# ES8388.net
KiCad netlist of a schematic drawn in Altium Designer
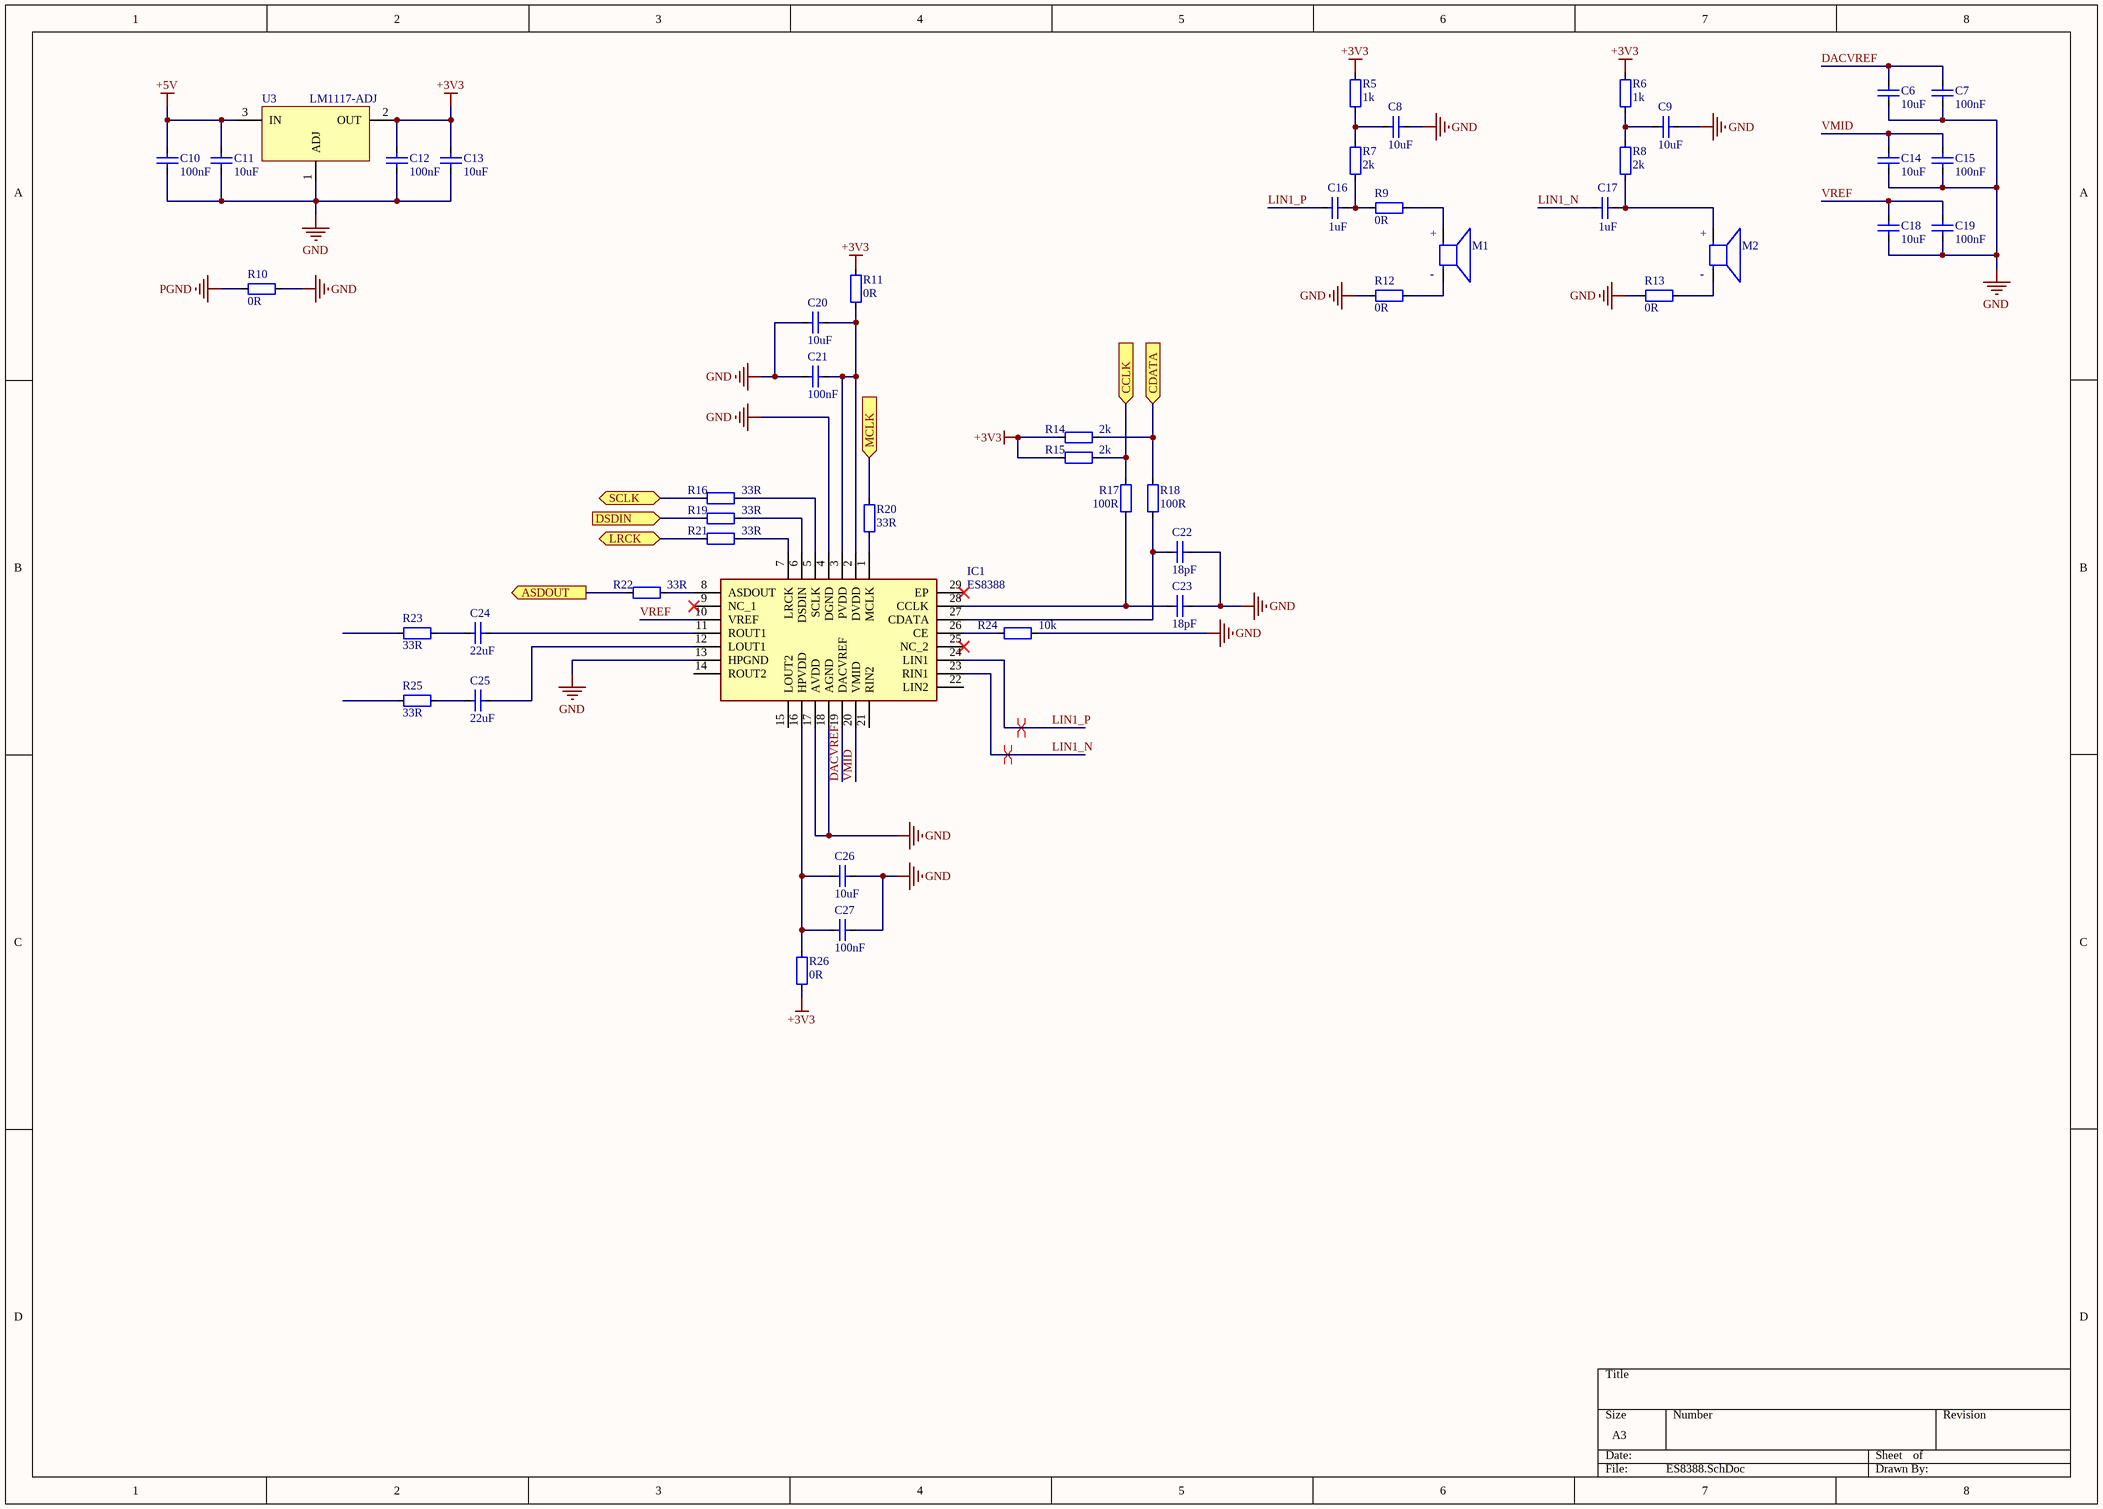
[diagram p0: ES8388.SchDoc]

(export (version "E")
  (design (tool "Eeschema 10.0.6"))
  (components
    (comp (ref "C6")
      (value "10uF")
      (footprint "CAP_0603")
      (description "Capacitor")
      (fields (field (name "PUBLISHER") "Altium Limited"))
      (libsource (lib "My Library") (part "CapSMD"))
    )
    (comp (ref "C7")
      (value "100nF")
      (footprint "CAP_0603")
      (description "Capacitor")
      (fields (field (name "PUBLISHER") "Altium Limited"))
      (libsource (lib "My Library") (part "CapSMD"))
    )
    (comp (ref "C8")
      (value "10uF")
      (footprint "CAP_0603")
      (description "Capacitor")
      (fields (field (name "PUBLISHER") "Altium Limited"))
      (libsource (lib "My Library") (part "CapSMD"))
    )
    (comp (ref "C9")
      (value "10uF")
      (footprint "CAP_0603")
      (description "Capacitor")
      (fields (field (name "PUBLISHER") "Altium Limited"))
      (libsource (lib "My Library") (part "CapSMD"))
    )
    (comp (ref "C10")
      (value "100nF")
      (footprint "CAP_0805")
      (description "Capacitor")
      (fields (field (name "PUBLISHER") "Altium Limited"))
      (libsource (lib "My Library") (part "CapSMD"))
    )
    (comp (ref "C11")
      (value "10uF")
      (footprint "CAP_0805")
      (description "Capacitor")
      (fields (field (name "PUBLISHER") "Altium Limited"))
      (libsource (lib "My Library") (part "CapSMD"))
    )
    (comp (ref "C12")
      (value "100nF")
      (footprint "CAP_0805")
      (description "Capacitor")
      (fields (field (name "PUBLISHER") "Altium Limited"))
      (libsource (lib "My Library") (part "CapSMD"))
    )
    (comp (ref "C13")
      (value "10uF")
      (footprint "CAP_0805")
      (description "Capacitor")
      (fields (field (name "PUBLISHER") "Altium Limited"))
      (libsource (lib "My Library") (part "CapSMD"))
    )
    (comp (ref "C14")
      (value "10uF")
      (footprint "CAP_0603")
      (description "Capacitor")
      (fields (field (name "PUBLISHER") "Altium Limited"))
      (libsource (lib "My Library") (part "CapSMD"))
    )
    (comp (ref "C15")
      (value "100nF")
      (footprint "CAP_0603")
      (description "Capacitor")
      (fields (field (name "PUBLISHER") "Altium Limited"))
      (libsource (lib "My Library") (part "CapSMD"))
    )
    (comp (ref "C16")
      (value "1uF")
      (footprint "CAP_0603")
      (description "Capacitor")
      (fields (field (name "PUBLISHER") "Altium Limited"))
      (libsource (lib "My Library") (part "CapSMD"))
    )
    (comp (ref "C17")
      (value "1uF")
      (footprint "CAP_0603")
      (description "Capacitor")
      (fields (field (name "PUBLISHER") "Altium Limited"))
      (libsource (lib "My Library") (part "CapSMD"))
    )
    (comp (ref "C18")
      (value "10uF")
      (footprint "CAP_0603")
      (description "Capacitor")
      (fields (field (name "PUBLISHER") "Altium Limited"))
      (libsource (lib "My Library") (part "CapSMD"))
    )
    (comp (ref "C19")
      (value "100nF")
      (footprint "CAP_0603")
      (description "Capacitor")
      (fields (field (name "PUBLISHER") "Altium Limited"))
      (libsource (lib "My Library") (part "CapSMD"))
    )
    (comp (ref "C20")
      (value "10uF")
      (footprint "CAP_0603")
      (description "Capacitor")
      (fields (field (name "PUBLISHER") "Altium Limited"))
      (libsource (lib "My Library") (part "CapSMD"))
    )
    (comp (ref "C21")
      (value "100nF")
      (footprint "CAP_0603")
      (description "Capacitor")
      (fields (field (name "PUBLISHER") "Altium Limited"))
      (libsource (lib "My Library") (part "CapSMD"))
    )
    (comp (ref "C22")
      (value "18pF")
      (footprint "CAP_0603")
      (description "Capacitor")
      (fields (field (name "PUBLISHER") "Altium Limited"))
      (libsource (lib "My Library") (part "CapSMD"))
    )
    (comp (ref "C23")
      (value "18pF")
      (footprint "CAP_0603")
      (description "Capacitor")
      (fields (field (name "PUBLISHER") "Altium Limited"))
      (libsource (lib "My Library") (part "CapSMD"))
    )
    (comp (ref "C24")
      (value "22uF")
      (footprint "CAP_0805")
      (description "Capacitor")
      (fields (field (name "PUBLISHER") "Altium Limited"))
      (libsource (lib "My Library") (part "CapSMD"))
    )
    (comp (ref "C25")
      (value "22uF")
      (footprint "CAP_0805")
      (description "Capacitor")
      (fields (field (name "PUBLISHER") "Altium Limited"))
      (libsource (lib "My Library") (part "CapSMD"))
    )
    (comp (ref "C26")
      (value "10uF")
      (footprint "CAP_0603")
      (description "Capacitor")
      (fields (field (name "PUBLISHER") "Altium Limited"))
      (libsource (lib "My Library") (part "CapSMD"))
    )
    (comp (ref "C27")
      (value "100nF")
      (footprint "CAP_0603")
      (description "Capacitor")
      (fields (field (name "PUBLISHER") "Altium Limited"))
      (libsource (lib "My Library") (part "CapSMD"))
    )
    (comp (ref "IC1") (value "ES8388") (footprint "ES8388") (libsource (lib "My Library") (part "ES8388")))
    (comp (ref "M1")
      (value "Microphone")
      (footprint "Microphone")
      (libsource (lib "My Library") (part "Microphone"))
    )
    (comp (ref "M2")
      (value "Microphone")
      (footprint "Microphone")
      (libsource (lib "My Library") (part "Microphone"))
    )
    (comp (ref "R5")
      (value "1k")
      (footprint "RES-SMD-0603")
      (description "Resistor")
      (fields
        (field (name "MANUFACTURER") "Generic Components")
        (field (name "PUBLISHER") "Altium Hobart Technology Centre")
      )
      (libsource (lib "My Library") (part "Resistor - SMD"))
    )
    (comp (ref "R6")
      (value "1k")
      (footprint "RES-SMD-0603")
      (description "Resistor")
      (fields
        (field (name "MANUFACTURER") "Generic Components")
        (field (name "PUBLISHER") "Altium Hobart Technology Centre")
      )
      (libsource (lib "My Library") (part "Resistor - SMD"))
    )
    (comp (ref "R7")
      (value "2k")
      (footprint "RES-SMD-0603")
      (description "Resistor")
      (fields
        (field (name "MANUFACTURER") "Generic Components")
        (field (name "PUBLISHER") "Altium Hobart Technology Centre")
      )
      (libsource (lib "My Library") (part "Resistor - SMD"))
    )
    (comp (ref "R8")
      (value "2k")
      (footprint "RES-SMD-0603")
      (description "Resistor")
      (fields
        (field (name "MANUFACTURER") "Generic Components")
        (field (name "PUBLISHER") "Altium Hobart Technology Centre")
      )
      (libsource (lib "My Library") (part "Resistor - SMD"))
    )
    (comp (ref "R9")
      (value "0R")
      (footprint "RES-SMD-0603")
      (description "Resistor")
      (fields
        (field (name "MANUFACTURER") "Generic Components")
        (field (name "PUBLISHER") "Altium Hobart Technology Centre")
      )
      (libsource (lib "My Library") (part "Resistor - SMD"))
    )
    (comp (ref "R10")
      (value "0R")
      (footprint "RES-SMD-0603")
      (description "Resistor")
      (fields
        (field (name "MANUFACTURER") "Generic Components")
        (field (name "PUBLISHER") "Altium Hobart Technology Centre")
      )
      (libsource (lib "My Library") (part "Resistor - SMD"))
    )
    (comp (ref "R11")
      (value "0R")
      (footprint "RES-SMD-0603")
      (description "Resistor")
      (fields
        (field (name "MANUFACTURER") "Generic Components")
        (field (name "PUBLISHER") "Altium Hobart Technology Centre")
      )
      (libsource (lib "My Library") (part "Resistor - SMD"))
    )
    (comp (ref "R12")
      (value "0R")
      (footprint "RES-SMD-0603")
      (description "Resistor")
      (fields
        (field (name "MANUFACTURER") "Generic Components")
        (field (name "PUBLISHER") "Altium Hobart Technology Centre")
      )
      (libsource (lib "My Library") (part "Resistor - SMD"))
    )
    (comp (ref "R13")
      (value "0R")
      (footprint "RES-SMD-0603")
      (description "Resistor")
      (fields
        (field (name "MANUFACTURER") "Generic Components")
        (field (name "PUBLISHER") "Altium Hobart Technology Centre")
      )
      (libsource (lib "My Library") (part "Resistor - SMD"))
    )
    (comp (ref "R14")
      (value "2k")
      (footprint "RES-SMD-0603")
      (description "Resistor")
      (fields
        (field (name "MANUFACTURER") "Generic Components")
        (field (name "PUBLISHER") "Altium Hobart Technology Centre")
      )
      (libsource (lib "My Library") (part "Resistor - SMD"))
    )
    (comp (ref "R15")
      (value "2k")
      (footprint "RES-SMD-0603")
      (description "Resistor")
      (fields
        (field (name "MANUFACTURER") "Generic Components")
        (field (name "PUBLISHER") "Altium Hobart Technology Centre")
      )
      (libsource (lib "My Library") (part "Resistor - SMD"))
    )
    (comp (ref "R16")
      (value "33R")
      (footprint "RES-SMD-0603")
      (description "Resistor")
      (fields
        (field (name "MANUFACTURER") "Generic Components")
        (field (name "PUBLISHER") "Altium Hobart Technology Centre")
      )
      (libsource (lib "My Library") (part "Resistor - SMD"))
    )
    (comp (ref "R17")
      (value "100R")
      (footprint "RES-SMD-0603")
      (description "Resistor")
      (fields
        (field (name "MANUFACTURER") "Generic Components")
        (field (name "PUBLISHER") "Altium Hobart Technology Centre")
      )
      (libsource (lib "My Library") (part "Resistor - SMD"))
    )
    (comp (ref "R18")
      (value "100R")
      (footprint "RES-SMD-0603")
      (description "Resistor")
      (fields
        (field (name "MANUFACTURER") "Generic Components")
        (field (name "PUBLISHER") "Altium Hobart Technology Centre")
      )
      (libsource (lib "My Library") (part "Resistor - SMD"))
    )
    (comp (ref "R19")
      (value "33R")
      (footprint "RES-SMD-0603")
      (description "Resistor")
      (fields
        (field (name "MANUFACTURER") "Generic Components")
        (field (name "PUBLISHER") "Altium Hobart Technology Centre")
      )
      (libsource (lib "My Library") (part "Resistor - SMD"))
    )
    (comp (ref "R20")
      (value "33R")
      (footprint "RES-SMD-0603")
      (description "Resistor")
      (fields
        (field (name "MANUFACTURER") "Generic Components")
        (field (name "PUBLISHER") "Altium Hobart Technology Centre")
      )
      (libsource (lib "My Library") (part "Resistor - SMD"))
    )
    (comp (ref "R21")
      (value "33R")
      (footprint "RES-SMD-0603")
      (description "Resistor")
      (fields
        (field (name "MANUFACTURER") "Generic Components")
        (field (name "PUBLISHER") "Altium Hobart Technology Centre")
      )
      (libsource (lib "My Library") (part "Resistor - SMD"))
    )
    (comp (ref "R22")
      (value "33R")
      (footprint "RES-SMD-0603")
      (description "Resistor")
      (fields
        (field (name "MANUFACTURER") "Generic Components")
        (field (name "PUBLISHER") "Altium Hobart Technology Centre")
      )
      (libsource (lib "My Library") (part "Resistor - SMD"))
    )
    (comp (ref "R23")
      (value "33R")
      (footprint "RES-SMD-0603")
      (description "Resistor")
      (fields
        (field (name "MANUFACTURER") "Generic Components")
        (field (name "PUBLISHER") "Altium Hobart Technology Centre")
      )
      (libsource (lib "My Library") (part "Resistor - SMD"))
    )
    (comp (ref "R24")
      (value "10k")
      (footprint "RES-SMD-0603")
      (description "Resistor")
      (fields
        (field (name "MANUFACTURER") "Generic Components")
        (field (name "PUBLISHER") "Altium Hobart Technology Centre")
      )
      (libsource (lib "My Library") (part "Resistor - SMD"))
    )
    (comp (ref "R25")
      (value "33R")
      (footprint "RES-SMD-0603")
      (description "Resistor")
      (fields
        (field (name "MANUFACTURER") "Generic Components")
        (field (name "PUBLISHER") "Altium Hobart Technology Centre")
      )
      (libsource (lib "My Library") (part "Resistor - SMD"))
    )
    (comp (ref "R26")
      (value "0R")
      (footprint "RES-SMD-0603")
      (description "Resistor")
      (fields
        (field (name "MANUFACTURER") "Generic Components")
        (field (name "PUBLISHER") "Altium Hobart Technology Centre")
      )
      (libsource (lib "My Library") (part "Resistor - SMD"))
    )
    (comp (ref "U3")
      (value "LM1117-ADJ")
      (footprint "LM1117-SOP")
      (description "800mA Low-Dropout Linear Regulator")
      (fields (field (name "CREATOR") "Nguyen Ba Bien"))
      (libsource (lib "My Library") (part "LM1117-ADJ"))
    )
  )
  (nets
    (net (code "1") (name "+3V3") (class "Default")
      (node (ref "C12") (pin "2") (pinfunction "2_2") (pintype "passive"))
      (node (ref "C13") (pin "2") (pinfunction "2_2") (pintype "passive"))
      (node (ref "R11") (pin "2") (pinfunction "2_2") (pintype "passive"))
      (node (ref "R14") (pin "1") (pinfunction "1_1") (pintype "passive"))
      (node (ref "R15") (pin "1") (pinfunction "1_1") (pintype "passive"))
      (node (ref "R26") (pin "1") (pinfunction "1_1") (pintype "passive"))
      (node (ref "R5") (pin "1") (pinfunction "1_1") (pintype "passive"))
      (node (ref "R6") (pin "1") (pinfunction "1_1") (pintype "passive"))
      (node (ref "U3") (pin "2") (pinfunction "OUT_2") (pintype "passive"))
    )
    (net (code "2") (name "+5V") (class "Default")
      (node (ref "C10") (pin "2") (pinfunction "2_2") (pintype "passive"))
      (node (ref "C11") (pin "2") (pinfunction "2_2") (pintype "passive"))
      (node (ref "U3") (pin "3") (pinfunction "IN_3") (pintype "passive"))
    )
    (net (code "3") (name "/ASDOUT") (class "Default")
      (node (ref "R22") (pin "1") (pinfunction "1_1") (pintype "passive"))
    )
    (net (code "4") (name "/CCLK") (class "Default")
      (node (ref "R15") (pin "2") (pinfunction "2_2") (pintype "passive"))
      (node (ref "R17") (pin "1") (pinfunction "1_1") (pintype "passive"))
    )
    (net (code "5") (name "/CDATA") (class "Default")
      (node (ref "R14") (pin "2") (pinfunction "2_2") (pintype "passive"))
      (node (ref "R18") (pin "1") (pinfunction "1_1") (pintype "passive"))
    )
    (net (code "6") (name "/DACVREF") (class "Default")
      (node (ref "C6") (pin "1") (pinfunction "1_1") (pintype "passive"))
      (node (ref "C7") (pin "2") (pinfunction "2_2") (pintype "passive"))
      (node (ref "IC1") (pin "19") (pinfunction "DACVREF_19") (pintype "passive"))
    )
    (net (code "7") (name "/DSDIN") (class "Default")
      (node (ref "R19") (pin "1") (pinfunction "1_1") (pintype "passive"))
    )
    (net (code "8") (name "/LIN1_N") (class "Default")
      (node (ref "C17") (pin "1") (pinfunction "1_1") (pintype "passive"))
      (node (ref "IC1") (pin "23") (pinfunction "RIN1_23") (pintype "passive"))
    )
    (net (code "9") (name "/LIN1_P") (class "Default")
      (node (ref "C16") (pin "1") (pinfunction "1_1") (pintype "passive"))
      (node (ref "IC1") (pin "24") (pinfunction "LIN1_24") (pintype "passive"))
    )
    (net (code "10") (name "/LRCK") (class "Default")
      (node (ref "R21") (pin "1") (pinfunction "1_1") (pintype "passive"))
    )
    (net (code "11") (name "/MCLK") (class "Default")
      (node (ref "R20") (pin "2") (pinfunction "2_2") (pintype "passive"))
    )
    (net (code "12") (name "/SCLK") (class "Default")
      (node (ref "R16") (pin "1") (pinfunction "1_1") (pintype "passive"))
    )
    (net (code "13") (name "/VMID") (class "Default")
      (node (ref "C14") (pin "1") (pinfunction "1_1") (pintype "passive"))
      (node (ref "C15") (pin "2") (pinfunction "2_2") (pintype "passive"))
      (node (ref "IC1") (pin "20") (pinfunction "VMID_20") (pintype "passive"))
    )
    (net (code "14") (name "/VREF") (class "Default")
      (node (ref "C18") (pin "1") (pinfunction "1_1") (pintype "passive"))
      (node (ref "C19") (pin "2") (pinfunction "2_2") (pintype "passive"))
      (node (ref "IC1") (pin "10") (pinfunction "VREF_10") (pintype "passive"))
    )
    (net (code "15") (name "GND") (class "Default")
      (node (ref "C10") (pin "1") (pinfunction "1_1") (pintype "passive"))
      (node (ref "C11") (pin "1") (pinfunction "1_1") (pintype "passive"))
      (node (ref "C12") (pin "1") (pinfunction "1_1") (pintype "passive"))
      (node (ref "C13") (pin "1") (pinfunction "1_1") (pintype "passive"))
      (node (ref "C14") (pin "2") (pinfunction "2_2") (pintype "passive"))
      (node (ref "C15") (pin "1") (pinfunction "1_1") (pintype "passive"))
      (node (ref "C18") (pin "2") (pinfunction "2_2") (pintype "passive"))
      (node (ref "C19") (pin "1") (pinfunction "1_1") (pintype "passive"))
      (node (ref "C20") (pin "2") (pinfunction "2_2") (pintype "passive"))
      (node (ref "C21") (pin "1") (pinfunction "1_1") (pintype "passive"))
      (node (ref "C22") (pin "2") (pinfunction "2_2") (pintype "passive"))
      (node (ref "C23") (pin "2") (pinfunction "2_2") (pintype "passive"))
      (node (ref "C26") (pin "1") (pinfunction "1_1") (pintype "passive"))
      (node (ref "C27") (pin "2") (pinfunction "2_2") (pintype "passive"))
      (node (ref "C6") (pin "2") (pinfunction "2_2") (pintype "passive"))
      (node (ref "C7") (pin "1") (pinfunction "1_1") (pintype "passive"))
      (node (ref "C8") (pin "1") (pinfunction "1_1") (pintype "passive"))
      (node (ref "C9") (pin "1") (pinfunction "1_1") (pintype "passive"))
      (node (ref "IC1") (pin "13") (pinfunction "HPGND_13") (pintype "passive"))
      (node (ref "IC1") (pin "17") (pinfunction "AVDD_17") (pintype "passive"))
      (node (ref "IC1") (pin "18") (pinfunction "AGND_18") (pintype "passive"))
      (node (ref "IC1") (pin "4") (pinfunction "DGND_4") (pintype "passive"))
      (node (ref "R10") (pin "1") (pinfunction "1_1") (pintype "passive"))
      (node (ref "R12") (pin "2") (pinfunction "2_2") (pintype "passive"))
      (node (ref "R13") (pin "2") (pinfunction "2_2") (pintype "passive"))
      (node (ref "R24") (pin "1") (pinfunction "1_1") (pintype "passive"))
      (node (ref "U3") (pin "1") (pinfunction "ADJ_1") (pintype "passive"))
    )
    (net (code "16") (name "Net-(C8-Pad2)") (class "Default")
      (node (ref "C8") (pin "2") (pinfunction "2_2") (pintype "passive"))
      (node (ref "R5") (pin "2") (pinfunction "2_2") (pintype "passive"))
      (node (ref "R7") (pin "1") (pinfunction "1_1") (pintype "passive"))
    )
    (net (code "17") (name "Net-(C9-Pad2)") (class "Default")
      (node (ref "C9") (pin "2") (pinfunction "2_2") (pintype "passive"))
      (node (ref "R6") (pin "2") (pinfunction "2_2") (pintype "passive"))
      (node (ref "R8") (pin "1") (pinfunction "1_1") (pintype "passive"))
    )
    (net (code "18") (name "Net-(C16-Pad2)") (class "Default")
      (node (ref "C16") (pin "2") (pinfunction "2_2") (pintype "passive"))
      (node (ref "R7") (pin "2") (pinfunction "2_2") (pintype "passive"))
      (node (ref "R9") (pin "2") (pinfunction "2_2") (pintype "passive"))
    )
    (net (code "19") (name "Net-(C24-Pad2)") (class "Default")
      (node (ref "C24") (pin "2") (pinfunction "2_2") (pintype "passive"))
      (node (ref "R23") (pin "1") (pinfunction "1_1") (pintype "passive"))
    )
    (net (code "20") (name "Net-(C25-Pad2)") (class "Default")
      (node (ref "C25") (pin "2") (pinfunction "2_2") (pintype "passive"))
      (node (ref "R25") (pin "1") (pinfunction "1_1") (pintype "passive"))
    )
    (net (code "21") (name "Net-(IC1-ASDOUT)") (class "Default")
      (node (ref "IC1") (pin "8") (pinfunction "ASDOUT_8") (pintype "passive"))
      (node (ref "R22") (pin "2") (pinfunction "2_2") (pintype "passive"))
    )
    (net (code "22") (name "Net-(IC1-CCLK)") (class "Default")
      (node (ref "C23") (pin "1") (pinfunction "1_1") (pintype "passive"))
      (node (ref "IC1") (pin "28") (pinfunction "CCLK_28") (pintype "passive"))
      (node (ref "R17") (pin "2") (pinfunction "2_2") (pintype "passive"))
    )
    (net (code "23") (name "Net-(IC1-CDATA)") (class "Default")
      (node (ref "C22") (pin "1") (pinfunction "1_1") (pintype "passive"))
      (node (ref "IC1") (pin "27") (pinfunction "CDATA_27") (pintype "passive"))
      (node (ref "R18") (pin "2") (pinfunction "2_2") (pintype "passive"))
    )
    (net (code "24") (name "Net-(IC1-CE)") (class "Default")
      (node (ref "IC1") (pin "26") (pinfunction "CE_26") (pintype "passive"))
      (node (ref "R24") (pin "2") (pinfunction "2_2") (pintype "passive"))
    )
    (net (code "25") (name "Net-(IC1-DSDIN)") (class "Default")
      (node (ref "IC1") (pin "6") (pinfunction "DSDIN_6") (pintype "passive"))
      (node (ref "R19") (pin "2") (pinfunction "2_2") (pintype "passive"))
    )
    (net (code "26") (name "Net-(IC1-DVDD)") (class "Default")
      (node (ref "C20") (pin "1") (pinfunction "1_1") (pintype "passive"))
      (node (ref "C21") (pin "2") (pinfunction "2_2") (pintype "passive"))
      (node (ref "IC1") (pin "2") (pinfunction "DVDD_2") (pintype "passive"))
      (node (ref "IC1") (pin "3") (pinfunction "PVDD_3") (pintype "passive"))
      (node (ref "R11") (pin "1") (pinfunction "1_1") (pintype "passive"))
    )
    (net (code "27") (name "Net-(IC1-HPVDD)") (class "Default")
      (node (ref "C26") (pin "2") (pinfunction "2_2") (pintype "passive"))
      (node (ref "C27") (pin "1") (pinfunction "1_1") (pintype "passive"))
      (node (ref "IC1") (pin "16") (pinfunction "HPVDD_16") (pintype "passive"))
      (node (ref "R26") (pin "2") (pinfunction "2_2") (pintype "passive"))
    )
    (net (code "28") (name "Net-(IC1-LOUT1)") (class "Default")
      (node (ref "C25") (pin "1") (pinfunction "1_1") (pintype "passive"))
      (node (ref "IC1") (pin "12") (pinfunction "LOUT1_12") (pintype "passive"))
    )
    (net (code "29") (name "Net-(IC1-LRCK)") (class "Default")
      (node (ref "IC1") (pin "7") (pinfunction "LRCK_7") (pintype "passive"))
      (node (ref "R21") (pin "2") (pinfunction "2_2") (pintype "passive"))
    )
    (net (code "30") (name "Net-(IC1-MCLK)") (class "Default")
      (node (ref "IC1") (pin "1") (pinfunction "MCLK_1") (pintype "passive"))
      (node (ref "R20") (pin "1") (pinfunction "1_1") (pintype "passive"))
    )
    (net (code "31") (name "Net-(IC1-ROUT1)") (class "Default")
      (node (ref "C24") (pin "1") (pinfunction "1_1") (pintype "passive"))
      (node (ref "IC1") (pin "11") (pinfunction "ROUT1_11") (pintype "passive"))
    )
    (net (code "32") (name "Net-(IC1-SCLK)") (class "Default")
      (node (ref "IC1") (pin "5") (pinfunction "SCLK_5") (pintype "passive"))
      (node (ref "R16") (pin "2") (pinfunction "2_2") (pintype "passive"))
    )
    (net (code "33") (name "Net-(M1-NEG)") (class "Default")
      (node (ref "M1") (pin "N") (pinfunction "NEG_N") (pintype "passive"))
      (node (ref "R12") (pin "1") (pinfunction "1_1") (pintype "passive"))
    )
    (net (code "34") (name "Net-(M1-POS)") (class "Default")
      (node (ref "M1") (pin "P") (pinfunction "POS_P") (pintype "passive"))
      (node (ref "R9") (pin "1") (pinfunction "1_1") (pintype "passive"))
    )
    (net (code "35") (name "Net-(M2-NEG)") (class "Default")
      (node (ref "M2") (pin "N") (pinfunction "NEG_N") (pintype "passive"))
      (node (ref "R13") (pin "1") (pinfunction "1_1") (pintype "passive"))
    )
    (net (code "36") (name "Net-(M2-POS)") (class "Default")
      (node (ref "C17") (pin "2") (pinfunction "2_2") (pintype "passive"))
      (node (ref "M2") (pin "P") (pinfunction "POS_P") (pintype "passive"))
      (node (ref "R8") (pin "2") (pinfunction "2_2") (pintype "passive"))
    )
    (net (code "37") (name "PGND") (class "Default")
      (node (ref "R10") (pin "2") (pinfunction "2_2") (pintype "passive"))
    )
    (net (code "38") (name "unconnected-(IC1-EP-Pad29)") (class "Default")
      (node (ref "IC1") (pin "29") (pinfunction "EP_29") (pintype "passive+no_connect"))
    )
    (net (code "39") (name "unconnected-(IC1-LIN2-Pad22)") (class "Default")
      (node (ref "IC1") (pin "22") (pinfunction "LIN2_22") (pintype "passive"))
    )
    (net (code "40") (name "unconnected-(IC1-LOUT2-Pad15)") (class "Default")
      (node (ref "IC1") (pin "15") (pinfunction "LOUT2_15") (pintype "passive"))
    )
    (net (code "41") (name "unconnected-(IC1-NC_1-Pad9)") (class "Default")
      (node (ref "IC1") (pin "9") (pinfunction "NC_1_9") (pintype "passive+no_connect"))
    )
    (net (code "42") (name "unconnected-(IC1-NC_2-Pad25)") (class "Default")
      (node (ref "IC1") (pin "25") (pinfunction "NC_2_25") (pintype "passive+no_connect"))
    )
    (net (code "43") (name "unconnected-(IC1-RIN2-Pad21)") (class "Default")
      (node (ref "IC1") (pin "21") (pinfunction "RIN2_21") (pintype "passive"))
    )
    (net (code "44") (name "unconnected-(IC1-ROUT2-Pad14)") (class "Default")
      (node (ref "IC1") (pin "14") (pinfunction "ROUT2_14") (pintype "passive"))
    )
    (net (code "45") (name "unconnected-(R23-Pad2)") (class "Default")
      (node (ref "R23") (pin "2") (pinfunction "2_2") (pintype "passive"))
    )
    (net (code "46") (name "unconnected-(R25-Pad2)") (class "Default")
      (node (ref "R25") (pin "2") (pinfunction "2_2") (pintype "passive"))
    )
  )
)
